# REMOT.net
KiCad netlist of a schematic drawn in EAGLE
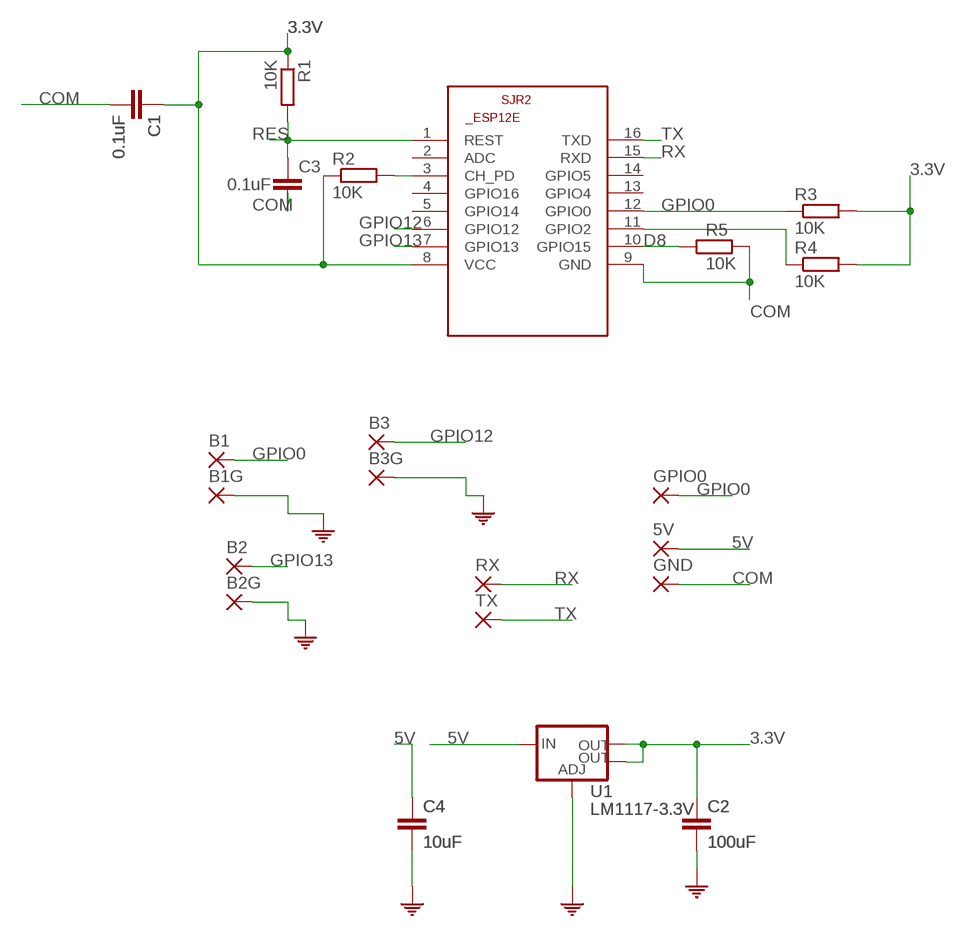
[diagram p0: schematic, sheet 1]

(export (version "E")
  (design (tool "Eeschema 10.0.6"))
  (components
    (comp (ref "5V")
      (value "SMD2")
      (footprint "eagle-import:SMD1,27-2,54")
      (libsource (lib "eagle-import") (part "SMD2"))
    )
    (comp (ref "B1")
      (value "SMD2")
      (footprint "eagle-import:SMD1,27-2,54")
      (libsource (lib "eagle-import") (part "SMD2"))
    )
    (comp (ref "B1G")
      (value "COM")
      (footprint "eagle-import:SMD1,27-2,54")
      (libsource (lib "eagle-import") (part "SMD2"))
    )
    (comp (ref "B2")
      (value "SMD2")
      (footprint "eagle-import:SMD1,27-2,54")
      (libsource (lib "eagle-import") (part "SMD2"))
    )
    (comp (ref "B2G")
      (value "SMD2")
      (footprint "eagle-import:SMD1,27-2,54")
      (libsource (lib "eagle-import") (part "SMD2"))
    )
    (comp (ref "B3")
      (value "SMD2")
      (footprint "eagle-import:SMD1,27-2,54")
      (libsource (lib "eagle-import") (part "SMD2"))
    )
    (comp (ref "B3G")
      (value "SMD2")
      (footprint "eagle-import:SMD1,27-2,54")
      (libsource (lib "eagle-import") (part "SMD2"))
    )
    (comp (ref "C1")
      (value "0.1uF")
      (footprint "eagle-import:C1206")
      (libsource (lib "eagle-import") (part "C-EUC1206"))
    )
    (comp (ref "C2")
      (value "100uF")
      (footprint "eagle-import:C1206")
      (libsource (lib "eagle-import") (part "C-EUC1206"))
    )
    (comp (ref "C3")
      (value "0.1uF")
      (footprint "eagle-import:C1206")
      (libsource (lib "eagle-import") (part "rcl_334_C-EUC1206"))
    )
    (comp (ref "C4")
      (value "10uF")
      (footprint "eagle-import:C1206")
      (libsource (lib "eagle-import") (part "C-EUC1206"))
    )
    (comp (ref "GND")
      (value "SMD2")
      (footprint "eagle-import:SMD1,27-2,54")
      (libsource (lib "eagle-import") (part "SMD2"))
    )
    (comp (ref "GPIO0")
      (value "SMD2")
      (footprint "eagle-import:SMD1,27-2,54")
      (libsource (lib "eagle-import") (part "SMD2"))
    )
    (comp (ref "R1")
      (value "10K")
      (footprint "eagle-import:R0805")
      (libsource (lib "eagle-import") (part "R-EU_R0805"))
    )
    (comp (ref "R2")
      (value "10K")
      (footprint "eagle-import:R0805")
      (libsource (lib "eagle-import") (part "R-EU_R0805"))
    )
    (comp (ref "R3")
      (value "10K")
      (footprint "eagle-import:R0805")
      (libsource (lib "eagle-import") (part "R-EU_R0805"))
    )
    (comp (ref "R4")
      (value "10K")
      (footprint "eagle-import:R0805")
      (libsource (lib "eagle-import") (part "R-EU_R0805"))
    )
    (comp (ref "R5")
      (value "10K")
      (footprint "eagle-import:R0805")
      (libsource (lib "eagle-import") (part "R-EU_R0805"))
    )
    (comp (ref "RX")
      (value "SMD2")
      (footprint "eagle-import:SMD1,27-2,54")
      (libsource (lib "eagle-import") (part "SMD2"))
    )
    (comp (ref "SJR2")
      (value "ESP8266-12EESP12E")
      (footprint "eagle-import:ESP8266-ESP12E")
      (libsource (lib "eagle-import") (part "ESP8266-12EESP12E"))
    )
    (comp (ref "TX")
      (value "SMD2")
      (footprint "eagle-import:SMD1,27-2,54")
      (libsource (lib "eagle-import") (part "SMD2"))
    )
    (comp (ref "U1")
      (value "LM1117-3.3V")
      (footprint "eagle-import:SOT223")
      (libsource (lib "eagle-import") (part "V_REG_LM1117SOT223"))
    )
  )
  (nets
    (net (code "1") (name "/3.3V") (class "Default")
      (node (ref "C1") (pin "1") (pinfunction "1_1") (pintype "passive"))
      (node (ref "C2") (pin "1") (pinfunction "1_1") (pintype "passive"))
      (node (ref "R1") (pin "1") (pinfunction "1_1") (pintype "passive"))
      (node (ref "R2") (pin "1") (pinfunction "1_1") (pintype "passive"))
      (node (ref "R3") (pin "2") (pinfunction "2_2") (pintype "passive"))
      (node (ref "R4") (pin "2") (pinfunction "2_2") (pintype "passive"))
      (node (ref "SJR2") (pin "8") (pinfunction "VCC_8") (pintype "bidirectional"))
      (node (ref "U1") (pin "2") (pinfunction "OUT_2") (pintype "output"))
      (node (ref "U1") (pin "4") (pinfunction "OUT_4") (pintype "output"))
    )
    (net (code "2") (name "/5V") (class "Default")
      (node (ref "5V") (pin "1") (pinfunction "P_1") (pintype "passive"))
      (node (ref "C4") (pin "1") (pinfunction "1_1") (pintype "passive"))
      (node (ref "U1") (pin "3") (pinfunction "IN_3") (pintype "input"))
    )
    (net (code "3") (name "/D8") (class "Default")
      (node (ref "R5") (pin "1") (pinfunction "1_1") (pintype "passive"))
      (node (ref "SJR2") (pin "10") (pinfunction "GPIO15_10") (pintype "bidirectional"))
    )
    (net (code "4") (name "/GPIO0") (class "Default")
      (node (ref "B1") (pin "1") (pinfunction "P_1") (pintype "passive"))
      (node (ref "GPIO0") (pin "1") (pinfunction "P_1") (pintype "passive"))
      (node (ref "R3") (pin "1") (pinfunction "1_1") (pintype "passive"))
      (node (ref "SJR2") (pin "12") (pinfunction "GPIO0_12") (pintype "bidirectional"))
    )
    (net (code "5") (name "/GPIO12") (class "Default")
      (node (ref "B3") (pin "1") (pinfunction "P_1") (pintype "passive"))
      (node (ref "SJR2") (pin "6") (pinfunction "GPIO12_6") (pintype "bidirectional"))
    )
    (net (code "6") (name "/GPIO13") (class "Default")
      (node (ref "B2") (pin "1") (pinfunction "P_1") (pintype "passive"))
      (node (ref "SJR2") (pin "7") (pinfunction "GPIO13_7") (pintype "bidirectional"))
    )
    (net (code "7") (name "/RES") (class "Default")
      (node (ref "C3") (pin "1") (pinfunction "1_1") (pintype "passive"))
      (node (ref "R1") (pin "2") (pinfunction "2_2") (pintype "passive"))
      (node (ref "SJR2") (pin "1") (pinfunction "REST_1") (pintype "bidirectional"))
    )
    (net (code "8") (name "/RX") (class "Default")
      (node (ref "RX") (pin "1") (pinfunction "P_1") (pintype "passive"))
      (node (ref "SJR2") (pin "15") (pinfunction "RXD_15") (pintype "bidirectional"))
    )
    (net (code "9") (name "/TX") (class "Default")
      (node (ref "SJR2") (pin "16") (pinfunction "TXD_16") (pintype "bidirectional"))
      (node (ref "TX") (pin "1") (pinfunction "P_1") (pintype "passive"))
    )
    (net (code "10") (name "COM") (class "Default")
      (node (ref "B1G") (pin "1") (pinfunction "P_1") (pintype "passive"))
      (node (ref "B2G") (pin "1") (pinfunction "P_1") (pintype "passive"))
      (node (ref "B3G") (pin "1") (pinfunction "P_1") (pintype "passive"))
      (node (ref "C1") (pin "2") (pinfunction "2_2") (pintype "passive"))
      (node (ref "C2") (pin "2") (pinfunction "2_2") (pintype "passive"))
      (node (ref "C3") (pin "2") (pinfunction "2_2") (pintype "passive"))
      (node (ref "C4") (pin "2") (pinfunction "2_2") (pintype "passive"))
      (node (ref "GND") (pin "1") (pinfunction "P_1") (pintype "passive"))
      (node (ref "R5") (pin "2") (pinfunction "2_2") (pintype "passive"))
      (node (ref "SJR2") (pin "9") (pinfunction "GND_9") (pintype "bidirectional"))
      (node (ref "U1") (pin "1") (pinfunction "ADJ_1") (pintype "input"))
    )
    (net (code "11") (name "Net-(SJR2-CH_PD)") (class "Default")
      (node (ref "R2") (pin "2") (pinfunction "2_2") (pintype "passive"))
      (node (ref "SJR2") (pin "3") (pinfunction "CH_PD_3") (pintype "bidirectional"))
    )
    (net (code "12") (name "Net-(SJR2-GPIO2)") (class "Default")
      (node (ref "R4") (pin "1") (pinfunction "1_1") (pintype "passive"))
      (node (ref "SJR2") (pin "11") (pinfunction "GPIO2_11") (pintype "bidirectional"))
    )
    (net (code "13") (name "unconnected-(SJR2-ADC-Pad2)") (class "Default")
      (node (ref "SJR2") (pin "2") (pinfunction "ADC_2") (pintype "bidirectional"))
    )
    (net (code "14") (name "unconnected-(SJR2-GPIO4-Pad13)") (class "Default")
      (node (ref "SJR2") (pin "13") (pinfunction "GPIO4_13") (pintype "bidirectional"))
    )
    (net (code "15") (name "unconnected-(SJR2-GPIO5-Pad14)") (class "Default")
      (node (ref "SJR2") (pin "14") (pinfunction "GPIO5_14") (pintype "bidirectional"))
    )
    (net (code "16") (name "unconnected-(SJR2-GPIO14-Pad5)") (class "Default")
      (node (ref "SJR2") (pin "5") (pinfunction "GPIO14_5") (pintype "bidirectional"))
    )
    (net (code "17") (name "unconnected-(SJR2-GPIO16-Pad4)") (class "Default")
      (node (ref "SJR2") (pin "4") (pinfunction "GPIO16_4") (pintype "bidirectional"))
    )
  )
)
